# jinkan_5m.net
KiCad netlist of a schematic drawn in EAGLE
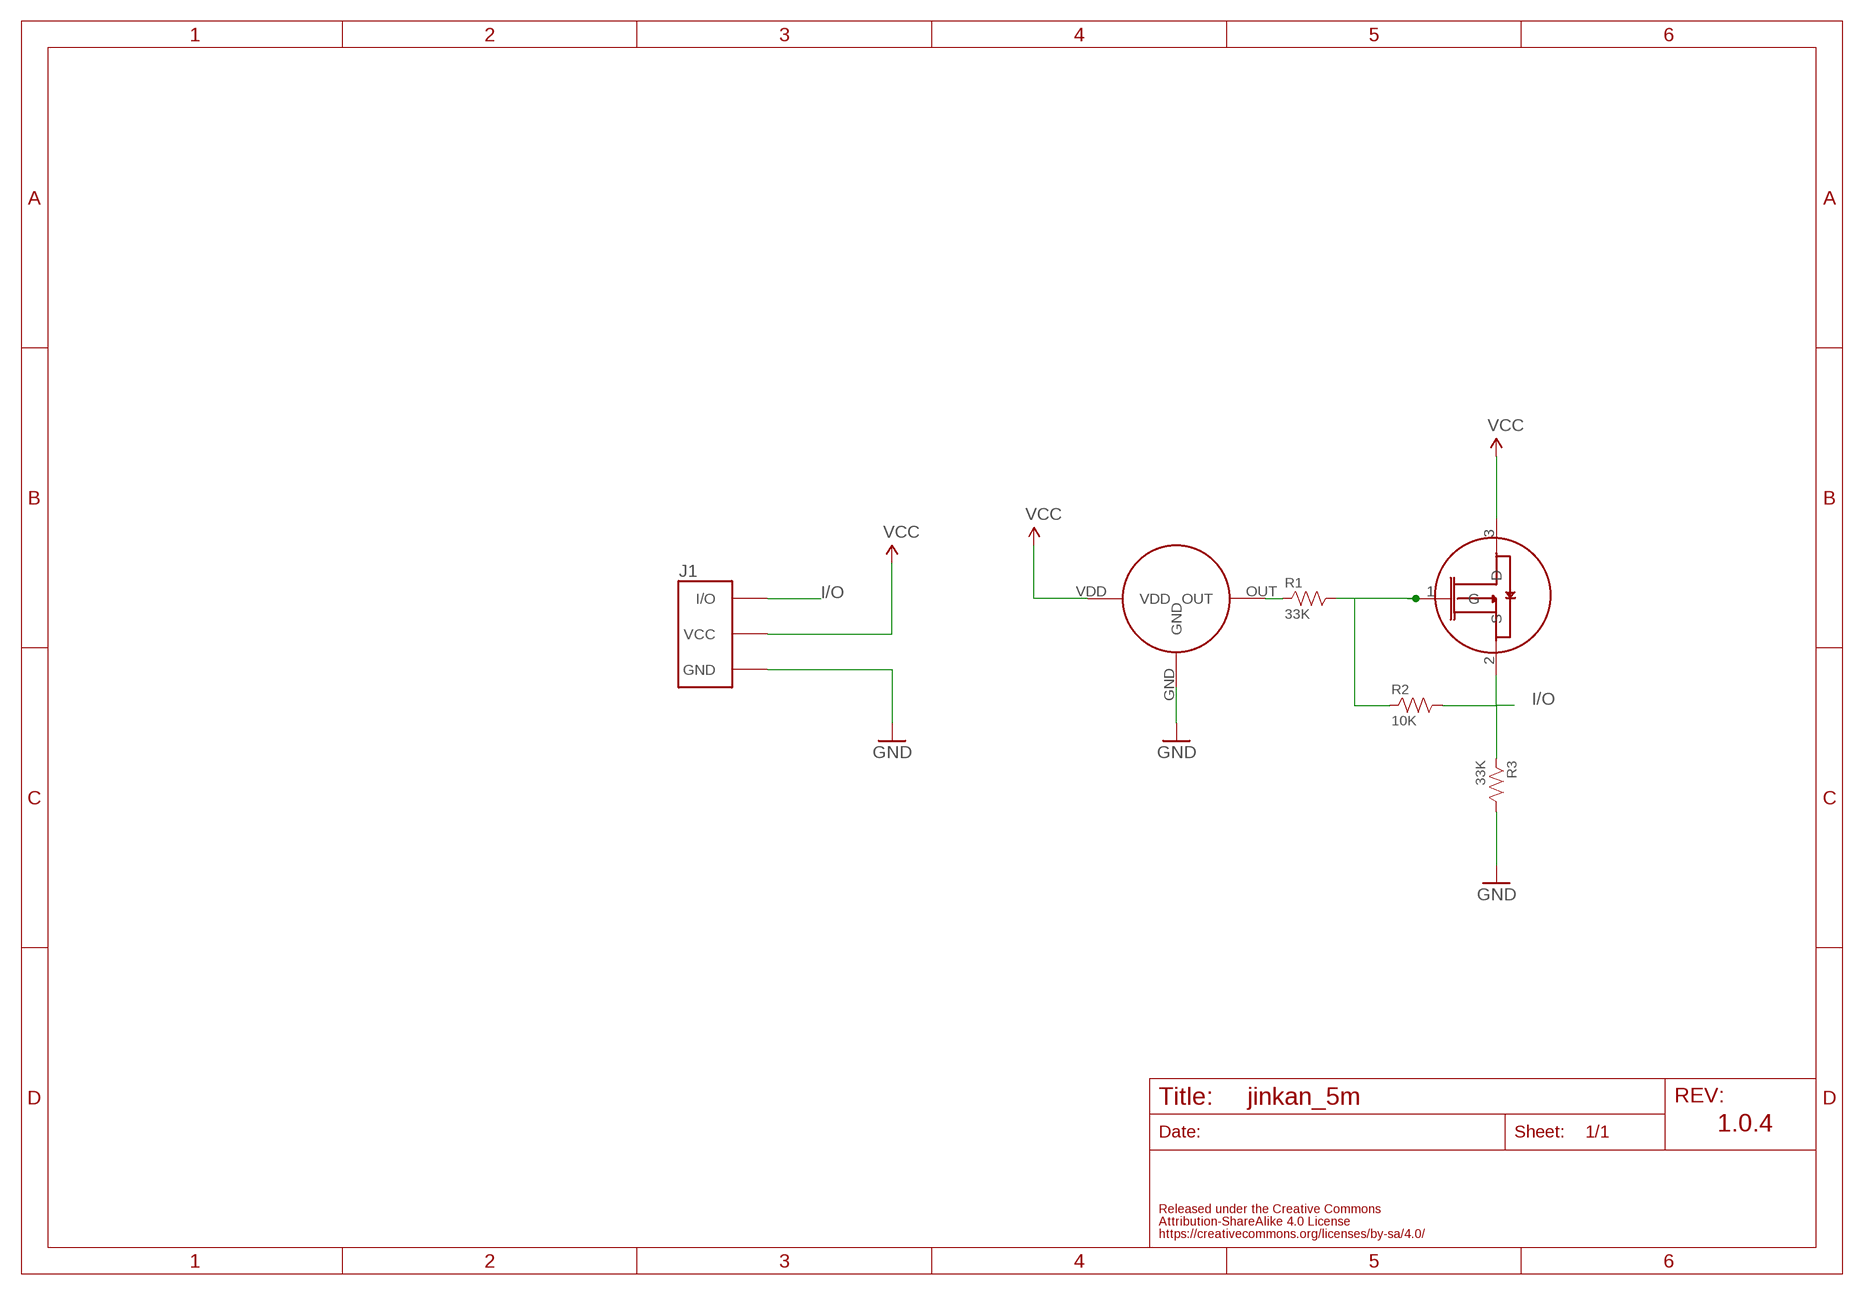
[diagram p0: schematic, sheet 1]

(export (version "E")
  (design (tool "Eeschema 10.0.6"))
  (components
    (comp (ref "J1")
      (value "FABO_BRICK_3PIN-B03-PASK-1_SILK_BOTTOM")
      (footprint "eagle-import:FABO_BRICK_3PIN_B03B-PASK-1_SILK_BOTTOM")
      (libsource (lib "eagle-import") (part "FABO_BRICK_3PIN-B03-PASK-1_SILK_BOTTOM"))
    )
    (comp (ref "R1")
      (value "33K")
      (footprint "eagle-import:0603")
      (libsource (lib "eagle-import") (part "RESISTOR-0603"))
    )
    (comp (ref "R2")
      (value "10K")
      (footprint "eagle-import:0603")
      (libsource (lib "eagle-import") (part "RESISTOR-0603"))
    )
    (comp (ref "R3")
      (value "33K")
      (footprint "eagle-import:0603")
      (libsource (lib "eagle-import") (part "RESISTOR-0603"))
    )
    (comp (ref "SW1")
      (value "FAIRCHILD-FDN338")
      (footprint "eagle-import:SOT23")
      (libsource (lib "eagle-import") (part "FAIRCHILD-FDN338"))
    )
    (comp (ref "U$4")
      (value "EKBM")
      (footprint "eagle-import:EKMB")
      (libsource (lib "eagle-import") (part "EKBM"))
    )
  )
  (nets
    (net (code "1") (name "/I{slash}O") (class "Default")
      (node (ref "J1") (pin "I/O") (pinfunction "I/O_I/O") (pintype "bidirectional"))
      (node (ref "R2") (pin "2") (pinfunction "2_2") (pintype "bidirectional"))
      (node (ref "R3") (pin "1") (pinfunction "1_1") (pintype "bidirectional"))
      (node (ref "SW1") (pin "2") (pinfunction "S_2") (pintype "input"))
    )
    (net (code "2") (name "GND") (class "Default")
      (node (ref "J1") (pin "GND") (pinfunction "GND_GND") (pintype "bidirectional"))
      (node (ref "R3") (pin "2") (pinfunction "2_2") (pintype "bidirectional"))
      (node (ref "U$4") (pin "GND") (pinfunction "GND_GND") (pintype "bidirectional"))
    )
    (net (code "3") (name "Net-(R1-Pad1)") (class "Default")
      (node (ref "R1") (pin "1") (pinfunction "1_1") (pintype "bidirectional"))
      (node (ref "U$4") (pin "OUT") (pinfunction "OUT_OUT") (pintype "bidirectional"))
    )
    (net (code "4") (name "Net-(SW1-G)") (class "Default")
      (node (ref "R1") (pin "2") (pinfunction "2_2") (pintype "bidirectional"))
      (node (ref "R2") (pin "1") (pinfunction "1_1") (pintype "bidirectional"))
      (node (ref "SW1") (pin "1") (pinfunction "G_1") (pintype "input"))
    )
    (net (code "5") (name "VCC") (class "Default")
      (node (ref "J1") (pin "VCC") (pinfunction "VCC_VCC") (pintype "bidirectional"))
      (node (ref "SW1") (pin "3") (pinfunction "D_3") (pintype "input"))
      (node (ref "U$4") (pin "VDD") (pinfunction "VDD_VDD") (pintype "bidirectional"))
    )
  )
)
